# Sheet1.net
KiCad netlist of a schematic drawn in Altium Designer
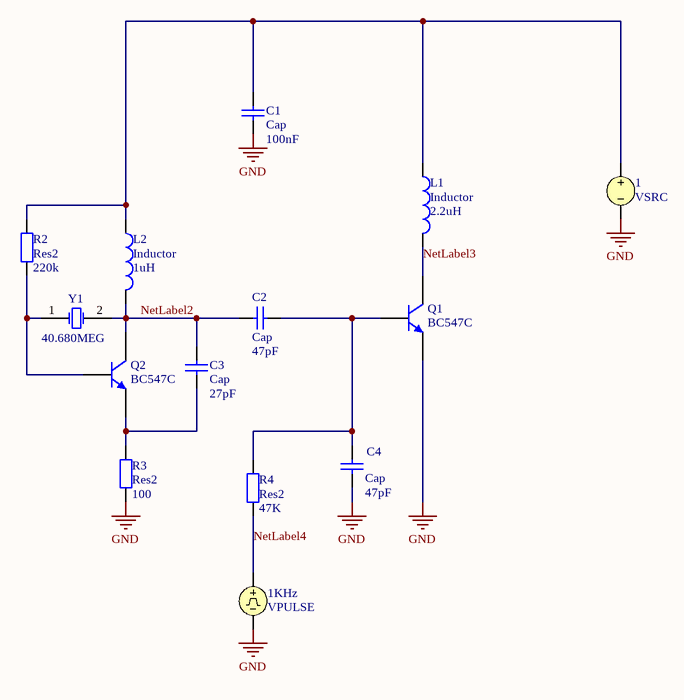
[diagram p0: Sheet1.SchDoc]

(export (version "E")
  (design (tool "Eeschema 10.0.6"))
  (components
    (comp (ref "1")
      (value "VSRC")
      (description "Voltage Source")
      (fields (field (name "PUBLISHER") "Altium Limited"))
      (libsource (lib "Simulation Sources") (part "VSRC"))
    )
    (comp (ref "1KHz")
      (value "VPULSE")
      (description "Pulse Voltage Source")
      (fields (field (name "PUBLISHER") "Altium Limited"))
      (libsource (lib "Simulation Sources") (part "VPULSE"))
    )
    (comp (ref "C1")
      (value "Cap")
      (footprint "RAD-0.3")
      (description "Capacitor")
      (fields (field (name "ALTIUM_VALUE") "100nF") (field (name "PUBLISHER") "Altium Limited"))
      (libsource (lib "Miscellaneous Devices") (part "Cap"))
    )
    (comp (ref "C2")
      (value "Cap")
      (footprint "RAD-0.3")
      (description "Capacitor")
      (fields (field (name "ALTIUM_VALUE") "47pF") (field (name "PUBLISHER") "Altium Limited"))
      (libsource (lib "Miscellaneous Devices") (part "Cap"))
    )
    (comp (ref "C3")
      (value "Cap")
      (footprint "RAD-0.3")
      (description "Capacitor")
      (fields (field (name "ALTIUM_VALUE") "27pF") (field (name "PUBLISHER") "Altium Limited"))
      (libsource (lib "Miscellaneous Devices") (part "Cap"))
    )
    (comp (ref "C4")
      (value "Cap")
      (footprint "RAD-0.3")
      (description "Capacitor")
      (fields (field (name "ALTIUM_VALUE") "47pF") (field (name "PUBLISHER") "Altium Limited"))
      (libsource (lib "Miscellaneous Devices") (part "Cap"))
    )
    (comp (ref "L1")
      (value "Inductor")
      (footprint "L0603")
      (fields (field (name "ALTIUM_VALUE") "2.2uH") (field (name "PUBLISHER") "Altium Limited"))
      (libsource (lib "Miscellaneous Devices") (part "Inductor"))
    )
    (comp (ref "L2")
      (value "Inductor")
      (footprint "L0603")
      (fields (field (name "ALTIUM_VALUE") "1uH") (field (name "PUBLISHER") "Altium Limited"))
      (libsource (lib "Miscellaneous Devices") (part "Inductor"))
    )
    (comp (ref "Q1")
      (value "BC547C")
      (footprint "SOT54")
      (description "NPN General-purpose Transistor")
      (fields (field (name "PUBLISHER") "Altium Limited"))
      (libsource (lib "Philips Discrete BJT - Low Power") (part "BC547C"))
    )
    (comp (ref "Q2")
      (value "BC547C")
      (footprint "SOT54")
      (description "NPN General-purpose Transistor")
      (fields (field (name "PUBLISHER") "Altium Limited"))
      (libsource (lib "Philips Discrete BJT - Low Power") (part "BC547C"))
    )
    (comp (ref "R2")
      (value "Res2")
      (footprint "AXIAL-0.4")
      (description "Resistor")
      (fields (field (name "ALTIUM_VALUE") "220k") (field (name "PUBLISHER") "Altium Limited"))
      (libsource (lib "Miscellaneous Devices") (part "Res2"))
    )
    (comp (ref "R3")
      (value "Res2")
      (footprint "AXIAL-0.4")
      (description "Resistor")
      (fields (field (name "ALTIUM_VALUE") "100") (field (name "PUBLISHER") "Altium Limited"))
      (libsource (lib "Miscellaneous Devices") (part "Res2"))
    )
    (comp (ref "R4")
      (value "Res2")
      (footprint "AXIAL-0.4")
      (description "Resistor")
      (fields (field (name "ALTIUM_VALUE") "47K") (field (name "PUBLISHER") "Altium Limited"))
      (libsource (lib "Miscellaneous Devices") (part "Res2"))
    )
    (comp (ref "Y1")
      (value "ECS-498.6-20-1")
      (footprint "HC-49U")
      (description "Crystal Oscillator")
      (fields (field (name "FREQ") "40.680MEG") (field (name "PUBLISHER") "Altium Limited"))
      (libsource (lib "ECS Crystal Oscillator") (part "ECS-498.6-20-1"))
    )
  )
  (nets
    (net (code "1") (name "/NetLabel2") (class "Default")
      (node (ref "C2") (pin "1") (pinfunction "1_1") (pintype "passive"))
      (node (ref "C3") (pin "2") (pinfunction "2_2") (pintype "passive"))
      (node (ref "L2") (pin "2") (pinfunction "2_2") (pintype "passive"))
      (node (ref "Q2") (pin "3") (pinfunction "C_3") (pintype "passive"))
      (node (ref "Y1") (pin "2") (pinfunction "OSC2_2") (pintype "passive"))
    )
    (net (code "2") (name "/NetLabel3") (class "Default")
      (node (ref "L1") (pin "2") (pinfunction "2_2") (pintype "passive"))
      (node (ref "Q1") (pin "3") (pinfunction "C_3") (pintype "passive"))
    )
    (net (code "3") (name "/NetLabel4") (class "Default")
      (node (ref "1KHz") (pin "1") (pinfunction "1_1") (pintype "passive"))
      (node (ref "R4") (pin "1") (pinfunction "1_1") (pintype "passive"))
    )
    (net (code "4") (name "GND") (class "Default")
      (node (ref "1") (pin "2") (pinfunction "2_2") (pintype "passive"))
      (node (ref "1KHz") (pin "2") (pinfunction "2_2") (pintype "passive"))
      (node (ref "C1") (pin "1") (pinfunction "1_1") (pintype "passive"))
      (node (ref "C4") (pin "1") (pinfunction "1_1") (pintype "passive"))
      (node (ref "Q1") (pin "1") (pinfunction "E_1") (pintype "passive"))
      (node (ref "R3") (pin "1") (pinfunction "1_1") (pintype "passive"))
    )
    (net (code "5") (name "Net-(1-Pad1)") (class "Default")
      (node (ref "1") (pin "1") (pinfunction "1_1") (pintype "passive"))
      (node (ref "C1") (pin "2") (pinfunction "2_2") (pintype "passive"))
      (node (ref "L1") (pin "1") (pinfunction "1_1") (pintype "passive"))
      (node (ref "L2") (pin "1") (pinfunction "1_1") (pintype "passive"))
      (node (ref "R2") (pin "2") (pinfunction "2_2") (pintype "passive"))
    )
    (net (code "6") (name "Net-(Q1-B)") (class "Default")
      (node (ref "C2") (pin "2") (pinfunction "2_2") (pintype "passive"))
      (node (ref "C4") (pin "2") (pinfunction "2_2") (pintype "passive"))
      (node (ref "Q1") (pin "2") (pinfunction "B_2") (pintype "passive"))
      (node (ref "R4") (pin "2") (pinfunction "2_2") (pintype "passive"))
    )
    (net (code "7") (name "Net-(Q2-B)") (class "Default")
      (node (ref "Q2") (pin "2") (pinfunction "B_2") (pintype "passive"))
      (node (ref "R2") (pin "1") (pinfunction "1_1") (pintype "passive"))
      (node (ref "Y1") (pin "1") (pinfunction "OSC1_1") (pintype "passive"))
    )
    (net (code "8") (name "Net-(Q2-E)") (class "Default")
      (node (ref "C3") (pin "1") (pinfunction "1_1") (pintype "passive"))
      (node (ref "Q2") (pin "1") (pinfunction "E_1") (pintype "passive"))
      (node (ref "R3") (pin "2") (pinfunction "2_2") (pintype "passive"))
    )
  )
)
